# USB2_0_USB3_0.net
KiCad netlist of a schematic drawn in Altium Designer
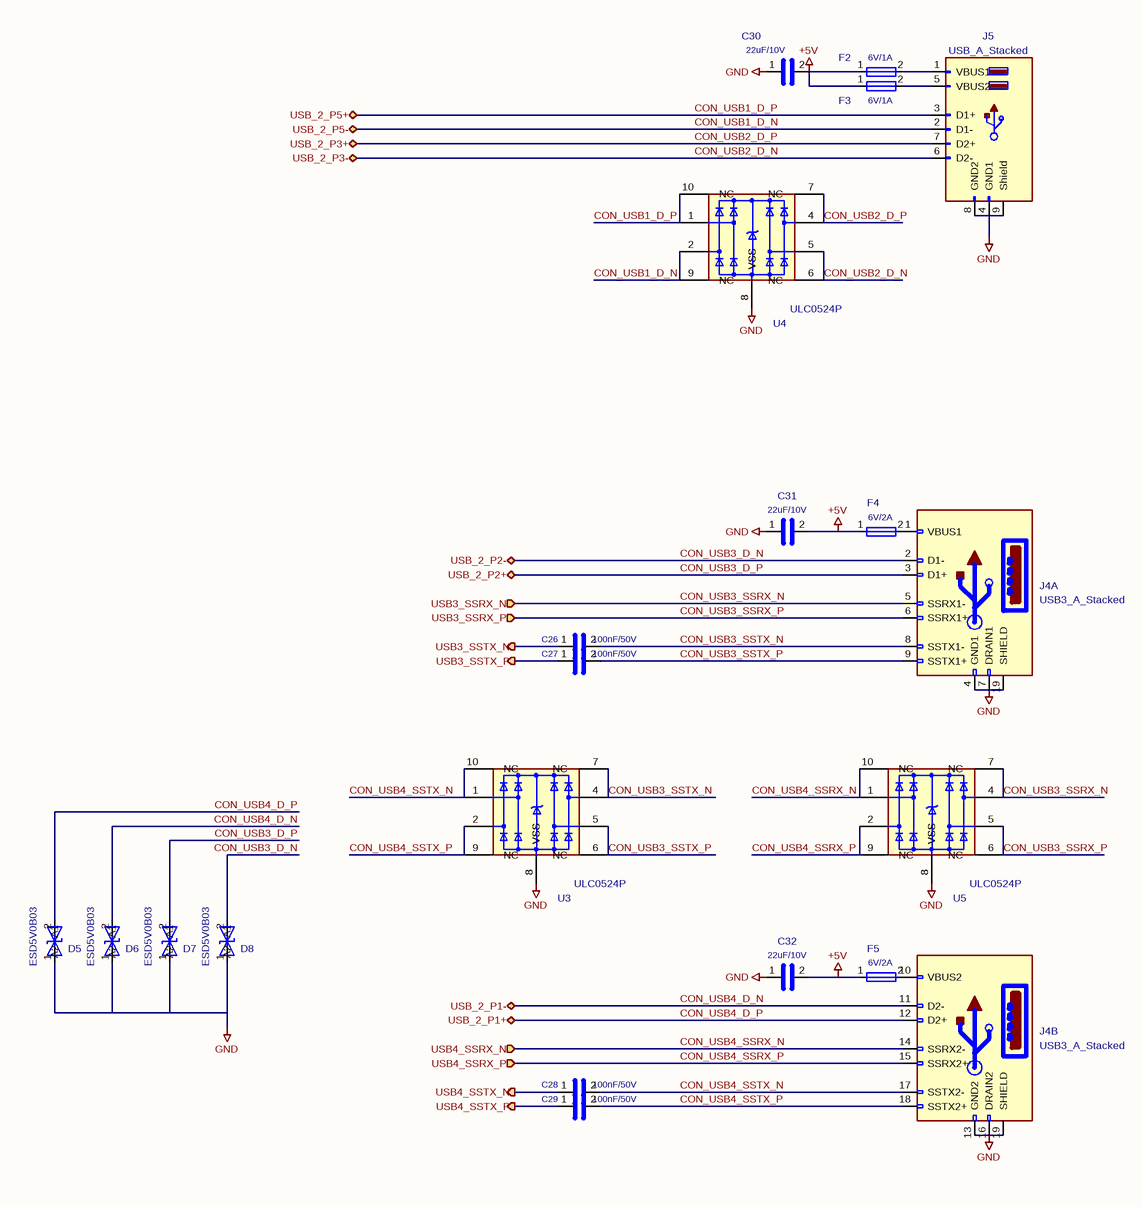
[diagram p0: USB2.0&USB3.0.SchDoc]

(export (version "E")
  (design (tool "Eeschema 10.0.6"))
  (components
    (comp (ref "C26") (value "100nF/50V") (libsource (lib "Device") (part "C")))
    (comp (ref "C27") (value "100nF/50V") (libsource (lib "Device") (part "C")))
    (comp (ref "C28") (value "100nF/50V") (libsource (lib "Device") (part "C")))
    (comp (ref "C29") (value "100nF/50V") (libsource (lib "Device") (part "C")))
    (comp (ref "C30") (value "22uF/10V") (libsource (lib "Device") (part "C")))
    (comp (ref "C31") (value "22uF/10V") (libsource (lib "Device") (part "C")))
    (comp (ref "C32") (value "22uF/10V") (libsource (lib "Device") (part "C")))
    (comp (ref "D5") (value "ESD5V0B03") (libsource (lib "Diode") (part "ESD9B5.0ST5G")))
    (comp (ref "D6") (value "ESD5V0B03") (libsource (lib "Diode") (part "ESD9B5.0ST5G")))
    (comp (ref "D7") (value "ESD5V0B03") (libsource (lib "Diode") (part "ESD9B5.0ST5G")))
    (comp (ref "D8") (value "ESD5V0B03") (libsource (lib "Diode") (part "ESD9B5.0ST5G")))
    (comp (ref "F2") (value "6V/1A") (libsource (lib "Device") (part "Fuse")))
    (comp (ref "F3") (value "6V/1A") (libsource (lib "Device") (part "Fuse")))
    (comp (ref "F4") (value "6V/2A") (libsource (lib "Device") (part "Fuse")))
    (comp (ref "F5") (value "6V/2A") (libsource (lib "Device") (part "Fuse")))
    (comp (ref "J4") (value "USB3_A_Stacked") (libsource (lib "Connector") (part "USB3_A_Stacked")))
    (comp (ref "J5") (value "USB_A_Stacked") (libsource (lib "Connector") (part "USB_A_Stacked")))
    (comp (ref "U3") (value "ULC0524P") (libsource (lib "Power_Protection") (part "D3V3XA4B10LP")))
    (comp (ref "U4") (value "ULC0524P") (libsource (lib "Power_Protection") (part "D3V3XA4B10LP")))
    (comp (ref "U5") (value "ULC0524P") (libsource (lib "Power_Protection") (part "D3V3XA4B10LP")))
  )
  (nets
    (net (code "1") (name "+5V") (class "Default")
      (node (ref "C30") (pin "2") (pinfunction "2_2") (pintype "passive"))
      (node (ref "C31") (pin "2") (pinfunction "2_2") (pintype "passive"))
      (node (ref "C32") (pin "2") (pinfunction "2_2") (pintype "passive"))
      (node (ref "F2") (pin "1") (pinfunction "1_1") (pintype "passive"))
      (node (ref "F3") (pin "1") (pinfunction "1_1") (pintype "passive"))
      (node (ref "F4") (pin "1") (pinfunction "1_1") (pintype "passive"))
      (node (ref "F5") (pin "1") (pinfunction "1_1") (pintype "passive"))
    )
    (net (code "2") (name "/CON_USB1_D_N") (class "Default")
      (node (ref "J5") (pin "2") (pinfunction "D1-_2") (pintype "passive"))
      (node (ref "U4") (pin "2") (pinfunction "2_2") (pintype "passive"))
      (node (ref "U4") (pin "9") (pinfunction "NC_9") (pintype "passive"))
    )
    (net (code "3") (name "/CON_USB1_D_P") (class "Default")
      (node (ref "J5") (pin "3") (pinfunction "D1+_3") (pintype "passive"))
      (node (ref "U4") (pin "1") (pinfunction "1_1") (pintype "passive"))
      (node (ref "U4") (pin "10") (pinfunction "NC_10") (pintype "passive"))
    )
    (net (code "4") (name "/CON_USB2_D_N") (class "Default")
      (node (ref "J5") (pin "6") (pinfunction "D2-_6") (pintype "passive"))
      (node (ref "U4") (pin "5") (pinfunction "5_5") (pintype "passive"))
      (node (ref "U4") (pin "6") (pinfunction "NC_6") (pintype "passive"))
    )
    (net (code "5") (name "/CON_USB2_D_P") (class "Default")
      (node (ref "J5") (pin "7") (pinfunction "D2+_7") (pintype "passive"))
      (node (ref "U4") (pin "4") (pinfunction "4_4") (pintype "passive"))
      (node (ref "U4") (pin "7") (pinfunction "NC_7") (pintype "passive"))
    )
    (net (code "6") (name "/CON_USB3_D_N") (class "Default")
      (node (ref "D8") (pin "2") (pinfunction "A2_2") (pintype "passive"))
      (node (ref "J4") (pin "2") (pinfunction "D1-_2") (pintype "passive"))
    )
    (net (code "7") (name "/CON_USB3_D_P") (class "Default")
      (node (ref "D7") (pin "2") (pinfunction "A2_2") (pintype "passive"))
      (node (ref "J4") (pin "3") (pinfunction "D1+_3") (pintype "passive"))
    )
    (net (code "8") (name "/CON_USB3_SSRX_N") (class "Default")
      (node (ref "J4") (pin "5") (pinfunction "SSRX1-_5") (pintype "passive"))
      (node (ref "U5") (pin "4") (pinfunction "4_4") (pintype "passive"))
      (node (ref "U5") (pin "7") (pinfunction "NC_7") (pintype "passive"))
    )
    (net (code "9") (name "/CON_USB3_SSRX_P") (class "Default")
      (node (ref "J4") (pin "6") (pinfunction "SSRX1+_6") (pintype "passive"))
      (node (ref "U5") (pin "5") (pinfunction "5_5") (pintype "passive"))
      (node (ref "U5") (pin "6") (pinfunction "NC_6") (pintype "passive"))
    )
    (net (code "10") (name "/CON_USB3_SSTX_N") (class "Default")
      (node (ref "C26") (pin "2") (pinfunction "2_2") (pintype "passive"))
      (node (ref "J4") (pin "8") (pinfunction "SSTX1-_8") (pintype "passive"))
      (node (ref "U3") (pin "4") (pinfunction "4_4") (pintype "passive"))
      (node (ref "U3") (pin "7") (pinfunction "NC_7") (pintype "passive"))
    )
    (net (code "11") (name "/CON_USB3_SSTX_P") (class "Default")
      (node (ref "C27") (pin "2") (pinfunction "2_2") (pintype "passive"))
      (node (ref "J4") (pin "9") (pinfunction "SSTX1+_9") (pintype "passive"))
      (node (ref "U3") (pin "5") (pinfunction "5_5") (pintype "passive"))
      (node (ref "U3") (pin "6") (pinfunction "NC_6") (pintype "passive"))
    )
    (net (code "12") (name "/CON_USB4_D_N") (class "Default")
      (node (ref "D6") (pin "2") (pinfunction "A2_2") (pintype "passive"))
      (node (ref "J4") (pin "11") (pinfunction "D2-_11") (pintype "passive"))
    )
    (net (code "13") (name "/CON_USB4_D_P") (class "Default")
      (node (ref "D5") (pin "2") (pinfunction "A2_2") (pintype "passive"))
      (node (ref "J4") (pin "12") (pinfunction "D2+_12") (pintype "passive"))
    )
    (net (code "14") (name "/CON_USB4_SSRX_N") (class "Default")
      (node (ref "J4") (pin "14") (pinfunction "SSRX2-_14") (pintype "passive"))
      (node (ref "U5") (pin "1") (pinfunction "1_1") (pintype "passive"))
      (node (ref "U5") (pin "10") (pinfunction "NC_10") (pintype "passive"))
    )
    (net (code "15") (name "/CON_USB4_SSRX_P") (class "Default")
      (node (ref "J4") (pin "15") (pinfunction "SSRX2+_15") (pintype "passive"))
      (node (ref "U5") (pin "2") (pinfunction "2_2") (pintype "passive"))
      (node (ref "U5") (pin "9") (pinfunction "NC_9") (pintype "passive"))
    )
    (net (code "16") (name "/CON_USB4_SSTX_N") (class "Default")
      (node (ref "C28") (pin "2") (pinfunction "2_2") (pintype "passive"))
      (node (ref "J4") (pin "17") (pinfunction "SSTX2-_17") (pintype "passive"))
      (node (ref "U3") (pin "1") (pinfunction "1_1") (pintype "passive"))
      (node (ref "U3") (pin "10") (pinfunction "NC_10") (pintype "passive"))
    )
    (net (code "17") (name "/CON_USB4_SSTX_P") (class "Default")
      (node (ref "C29") (pin "2") (pinfunction "2_2") (pintype "passive"))
      (node (ref "J4") (pin "18") (pinfunction "SSTX2+_18") (pintype "passive"))
      (node (ref "U3") (pin "2") (pinfunction "2_2") (pintype "passive"))
      (node (ref "U3") (pin "9") (pinfunction "NC_9") (pintype "passive"))
    )
    (net (code "18") (name "/USB3_SSTX_N") (class "Default")
      (node (ref "C26") (pin "1") (pinfunction "1_1") (pintype "passive"))
    )
    (net (code "19") (name "/USB3_SSTX_P") (class "Default")
      (node (ref "C27") (pin "1") (pinfunction "1_1") (pintype "passive"))
    )
    (net (code "20") (name "/USB4_SSTX_N") (class "Default")
      (node (ref "C28") (pin "1") (pinfunction "1_1") (pintype "passive"))
    )
    (net (code "21") (name "/USB4_SSTX_P") (class "Default")
      (node (ref "C29") (pin "1") (pinfunction "1_1") (pintype "passive"))
    )
    (net (code "22") (name "GND") (class "Default")
      (node (ref "C30") (pin "1") (pinfunction "1_1") (pintype "passive"))
      (node (ref "C31") (pin "1") (pinfunction "1_1") (pintype "passive"))
      (node (ref "C32") (pin "1") (pinfunction "1_1") (pintype "passive"))
      (node (ref "D5") (pin "1") (pinfunction "A1_1") (pintype "passive"))
      (node (ref "D6") (pin "1") (pinfunction "A1_1") (pintype "passive"))
      (node (ref "D7") (pin "1") (pinfunction "A1_1") (pintype "passive"))
      (node (ref "D8") (pin "1") (pinfunction "A1_1") (pintype "passive"))
      (node (ref "J4") (pin "13") (pinfunction "GND2_13") (pintype "passive"))
      (node (ref "J4") (pin "16") (pinfunction "DRAIN2_16") (pintype "passive"))
      (node (ref "J4") (pin "19") (pinfunction "SHIELD_19") (pintype "passive"))
      (node (ref "J4") (pin "4") (pinfunction "GND1_4") (pintype "passive"))
      (node (ref "J4") (pin "7") (pinfunction "DRAIN1_7") (pintype "passive"))
      (node (ref "J5") (pin "4") (pinfunction "GND1_4") (pintype "passive"))
      (node (ref "J5") (pin "8") (pinfunction "GND2_8") (pintype "passive"))
      (node (ref "J5") (pin "9") (pinfunction "Shield_9") (pintype "passive"))
      (node (ref "U3") (pin "3") (pinfunction "VSS_3") (pintype "passive"))
      (node (ref "U3") (pin "8") (pinfunction "VSS_8") (pintype "passive"))
      (node (ref "U4") (pin "3") (pinfunction "VSS_3") (pintype "passive"))
      (node (ref "U4") (pin "8") (pinfunction "VSS_8") (pintype "passive"))
      (node (ref "U5") (pin "3") (pinfunction "VSS_3") (pintype "passive"))
      (node (ref "U5") (pin "8") (pinfunction "VSS_8") (pintype "passive"))
    )
    (net (code "23") (name "Net-(J4A-VBUS1)") (class "Default")
      (node (ref "F4") (pin "2") (pinfunction "2_2") (pintype "passive"))
      (node (ref "J4") (pin "1") (pinfunction "VBUS1_1") (pintype "passive"))
    )
    (net (code "24") (name "Net-(J4B-VBUS2)") (class "Default")
      (node (ref "F5") (pin "2") (pinfunction "2_2") (pintype "passive"))
      (node (ref "J4") (pin "10") (pinfunction "VBUS2_10") (pintype "passive"))
    )
    (net (code "25") (name "Net-(J5-VBUS1)") (class "Default")
      (node (ref "F2") (pin "2") (pinfunction "2_2") (pintype "passive"))
      (node (ref "J5") (pin "1") (pinfunction "VBUS1_1") (pintype "passive"))
    )
    (net (code "26") (name "Net-(J5-VBUS2)") (class "Default")
      (node (ref "F3") (pin "2") (pinfunction "2_2") (pintype "passive"))
      (node (ref "J5") (pin "5") (pinfunction "VBUS2_5") (pintype "passive"))
    )
  )
)
